# planty1.net
KiCad netlist of a schematic drawn in EAGLE
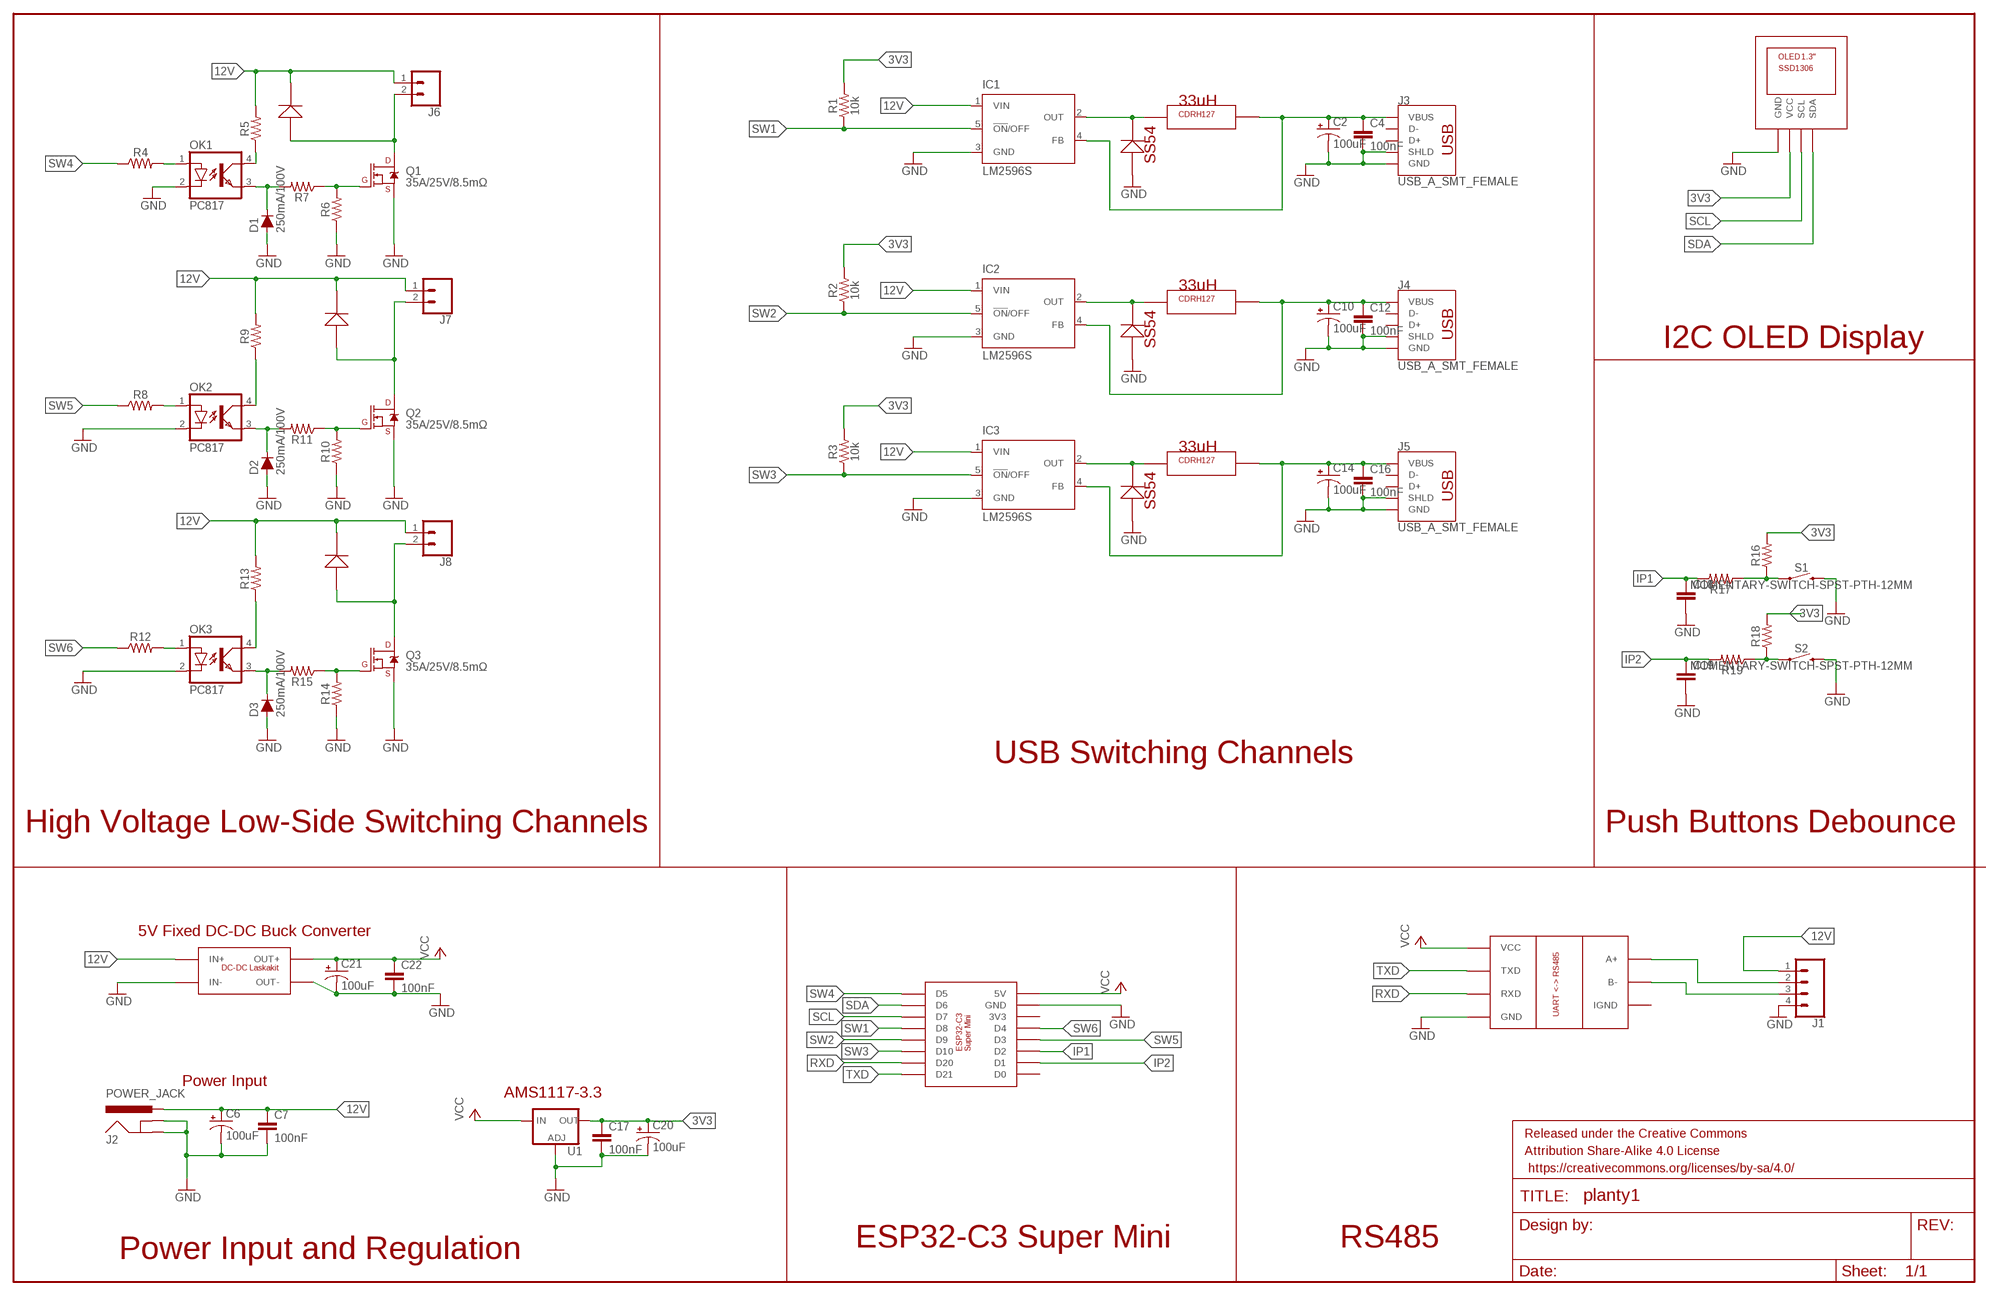
[diagram p0: schematic, sheet 1]

(export (version "E")
  (design (tool "Eeschema 10.0.6"))
  (components
    (comp (ref "C2")
      (value "100uF")
      (footprint "eagle-import:CPOL-RADIAL-2.5MM-6.5MM")
      (libsource (lib "eagle-import") (part "100UF-POLAR-RADIAL-2.5MM-25V-20%"))
    )
    (comp (ref "C4")
      (value "100nF")
      (footprint "eagle-import:1206")
      (libsource (lib "eagle-import") (part "CAP-1206"))
    )
    (comp (ref "C6")
      (value "100uF")
      (footprint "eagle-import:CPOL-RADIAL-2.5MM-6.5MM")
      (libsource (lib "eagle-import") (part "100UF-POLAR-RADIAL-2.5MM-25V-20%"))
    )
    (comp (ref "C7")
      (value "100nF")
      (footprint "eagle-import:1206")
      (libsource (lib "eagle-import") (part "CAP-1206"))
    )
    (comp (ref "C10")
      (value "100uF")
      (footprint "eagle-import:CPOL-RADIAL-2.5MM-6.5MM")
      (libsource (lib "eagle-import") (part "100UF-POLAR-RADIAL-2.5MM-25V-20%"))
    )
    (comp (ref "C12")
      (value "100nF")
      (footprint "eagle-import:1206")
      (libsource (lib "eagle-import") (part "CAP-1206"))
    )
    (comp (ref "C14")
      (value "100uF")
      (footprint "eagle-import:CPOL-RADIAL-2.5MM-6.5MM")
      (libsource (lib "eagle-import") (part "100UF-POLAR-RADIAL-2.5MM-25V-20%"))
    )
    (comp (ref "C16")
      (value "100nF")
      (footprint "eagle-import:1206")
      (libsource (lib "eagle-import") (part "CAP-1206"))
    )
    (comp (ref "C17")
      (value "100nF")
      (footprint "eagle-import:0603")
      (libsource (lib "eagle-import") (part "CAP-0603"))
    )
    (comp (ref "C18")
      (value "CAP-0603")
      (footprint "eagle-import:0603")
      (libsource (lib "eagle-import") (part "CAP-0603"))
    )
    (comp (ref "C19")
      (value "CAP-0603")
      (footprint "eagle-import:0603")
      (libsource (lib "eagle-import") (part "CAP-0603"))
    )
    (comp (ref "C20")
      (value "100uF")
      (footprint "eagle-import:CPOL-RADIAL-2.5MM-6.5MM")
      (libsource (lib "eagle-import") (part "100UF-POLAR-RADIAL-2.5MM-25V-20%"))
    )
    (comp (ref "C21")
      (value "100uF")
      (footprint "eagle-import:CPOL-RADIAL-2.5MM-6.5MM")
      (libsource (lib "eagle-import") (part "100UF-POLAR-RADIAL-2.5MM-25V-20%"))
    )
    (comp (ref "C22")
      (value "100nF")
      (footprint "eagle-import:1206")
      (libsource (lib "eagle-import") (part "CAP-1206"))
    )
    (comp (ref "D1")
      (value "250mA/100V")
      (footprint "eagle-import:SOD-323")
      (libsource (lib "eagle-import") (part "DIODE-BAS16J"))
    )
    (comp (ref "D2")
      (value "250mA/100V")
      (footprint "eagle-import:SOD-323")
      (libsource (lib "eagle-import") (part "DIODE-BAS16J"))
    )
    (comp (ref "D3")
      (value "250mA/100V")
      (footprint "eagle-import:SOD-323")
      (libsource (lib "eagle-import") (part "DIODE-BAS16J"))
    )
    (comp (ref "FRAME1")
      (value "FRAME-LEDGERNO_FOOTPRINT")
      (footprint "eagle-import:DUMMY")
      (libsource (lib "eagle-import") (part "FRAME-LEDGERNO_FOOTPRINT"))
    )
    (comp (ref "IC1")
      (value "LM2596S")
      (footprint "eagle-import:TO263-5")
      (fields (field (name "MF") "NATIONAL SEMICONDUCTOR") (field (name "MPN") "LM2596S-ADJ/NOPB"))
      (libsource (lib "eagle-import") (part "LM2596S"))
    )
    (comp (ref "IC2")
      (value "LM2596S")
      (footprint "eagle-import:TO263-5")
      (fields (field (name "MF") "NATIONAL SEMICONDUCTOR") (field (name "MPN") "LM2596S-ADJ/NOPB"))
      (libsource (lib "eagle-import") (part "LM2596S"))
    )
    (comp (ref "IC3")
      (value "LM2596S")
      (footprint "eagle-import:TO263-5")
      (fields (field (name "MF") "NATIONAL SEMICONDUCTOR") (field (name "MPN") "LM2596S-ADJ/NOPB"))
      (libsource (lib "eagle-import") (part "LM2596S"))
    )
    (comp (ref "J1")
      (value "CONN_04SCREW_LOCK")
      (footprint "eagle-import:SCREWTERMINAL-3.5MM-4_LOCK")
      (libsource (lib "eagle-import") (part "CONN_04SCREW_LOCK"))
    )
    (comp (ref "J2")
      (value "POWER_JACK")
      (footprint "eagle-import:POWER_JACK_PTH")
      (libsource (lib "eagle-import") (part "POWER_JACK"))
    )
    (comp (ref "J3")
      (value "USB_A_SMT_FEMALE")
      (footprint "eagle-import:USB-A-S-SILK-FEMALE")
      (libsource (lib "eagle-import") (part "USB_A_SMT_FEMALE"))
    )
    (comp (ref "J4")
      (value "USB_A_SMT_FEMALE")
      (footprint "eagle-import:USB-A-S-SILK-FEMALE")
      (libsource (lib "eagle-import") (part "USB_A_SMT_FEMALE"))
    )
    (comp (ref "J5")
      (value "USB_A_SMT_FEMALE")
      (footprint "eagle-import:USB-A-S-SILK-FEMALE")
      (libsource (lib "eagle-import") (part "USB_A_SMT_FEMALE"))
    )
    (comp (ref "J6")
      (value "CONN_025MM")
      (footprint "eagle-import:SCREWTERMINAL-5MM-2")
      (libsource (lib "eagle-import") (part "CONN_025MM"))
    )
    (comp (ref "J7")
      (value "CONN_025MM")
      (footprint "eagle-import:SCREWTERMINAL-5MM-2")
      (libsource (lib "eagle-import") (part "CONN_025MM"))
    )
    (comp (ref "J8")
      (value "CONN_025MM")
      (footprint "eagle-import:SCREWTERMINAL-5MM-2")
      (libsource (lib "eagle-import") (part "CONN_025MM"))
    )
    (comp (ref "OK1")
      (value "PC817")
      (footprint "eagle-import:DIL04")
      (fields (field (name "MPN") "PC817X4J000F"))
      (libsource (lib "eagle-import") (part "PC817"))
    )
    (comp (ref "OK2")
      (value "PC817")
      (footprint "eagle-import:DIL04")
      (fields (field (name "MPN") "PC817X4J000F"))
      (libsource (lib "eagle-import") (part "PC817"))
    )
    (comp (ref "OK3")
      (value "PC817")
      (footprint "eagle-import:DIL04")
      (fields (field (name "MPN") "PC817X4J000F"))
      (libsource (lib "eagle-import") (part "PC817"))
    )
    (comp (ref "Q1")
      (value "35A/25V/8.5mΩ")
      (footprint "eagle-import:TO-252_DPAK")
      (libsource (lib "eagle-import") (part "MOSFET-NCH-FDD8780"))
    )
    (comp (ref "Q2")
      (value "35A/25V/8.5mΩ")
      (footprint "eagle-import:TO-252_DPAK")
      (libsource (lib "eagle-import") (part "MOSFET-NCH-FDD8780"))
    )
    (comp (ref "Q3")
      (value "35A/25V/8.5mΩ")
      (footprint "eagle-import:TO-252_DPAK")
      (libsource (lib "eagle-import") (part "MOSFET-NCH-FDD8780"))
    )
    (comp (ref "R1")
      (value "10k")
      (footprint "eagle-import:0603")
      (libsource (lib "eagle-import") (part "RESISTOR0603"))
    )
    (comp (ref "R2")
      (value "10k")
      (footprint "eagle-import:0603")
      (libsource (lib "eagle-import") (part "RESISTOR0603"))
    )
    (comp (ref "R3")
      (value "10k")
      (footprint "eagle-import:0603")
      (libsource (lib "eagle-import") (part "RESISTOR0603"))
    )
    (comp (ref "R4")
      (value "RESISTOR0603")
      (footprint "eagle-import:0603")
      (libsource (lib "eagle-import") (part "RESISTOR0603"))
    )
    (comp (ref "R5")
      (value "RESISTOR0603")
      (footprint "eagle-import:0603")
      (libsource (lib "eagle-import") (part "RESISTOR0603"))
    )
    (comp (ref "R6")
      (value "RESISTOR0603")
      (footprint "eagle-import:0603")
      (libsource (lib "eagle-import") (part "RESISTOR0603"))
    )
    (comp (ref "R7")
      (value "RESISTOR0603")
      (footprint "eagle-import:0603")
      (libsource (lib "eagle-import") (part "RESISTOR0603"))
    )
    (comp (ref "R8")
      (value "RESISTOR0603")
      (footprint "eagle-import:0603")
      (libsource (lib "eagle-import") (part "RESISTOR0603"))
    )
    (comp (ref "R9")
      (value "RESISTOR0603")
      (footprint "eagle-import:0603")
      (libsource (lib "eagle-import") (part "RESISTOR0603"))
    )
    (comp (ref "R10")
      (value "RESISTOR0603")
      (footprint "eagle-import:0603")
      (libsource (lib "eagle-import") (part "RESISTOR0603"))
    )
    (comp (ref "R11")
      (value "RESISTOR0603")
      (footprint "eagle-import:0603")
      (libsource (lib "eagle-import") (part "RESISTOR0603"))
    )
    (comp (ref "R12")
      (value "RESISTOR0603")
      (footprint "eagle-import:0603")
      (libsource (lib "eagle-import") (part "RESISTOR0603"))
    )
    (comp (ref "R13")
      (value "RESISTOR0603")
      (footprint "eagle-import:0603")
      (libsource (lib "eagle-import") (part "RESISTOR0603"))
    )
    (comp (ref "R14")
      (value "RESISTOR0603")
      (footprint "eagle-import:0603")
      (libsource (lib "eagle-import") (part "RESISTOR0603"))
    )
    (comp (ref "R15")
      (value "RESISTOR0603")
      (footprint "eagle-import:0603")
      (libsource (lib "eagle-import") (part "RESISTOR0603"))
    )
    (comp (ref "R16")
      (value "RESISTOR0603")
      (footprint "eagle-import:0603")
      (libsource (lib "eagle-import") (part "RESISTOR0603"))
    )
    (comp (ref "R17")
      (value "RESISTOR0603")
      (footprint "eagle-import:0603")
      (libsource (lib "eagle-import") (part "RESISTOR0603"))
    )
    (comp (ref "R18")
      (value "RESISTOR0603")
      (footprint "eagle-import:0603")
      (libsource (lib "eagle-import") (part "RESISTOR0603"))
    )
    (comp (ref "R19")
      (value "RESISTOR0603")
      (footprint "eagle-import:0603")
      (libsource (lib "eagle-import") (part "RESISTOR0603"))
    )
    (comp (ref "S1")
      (value "MOMENTARY-SWITCH-SPST-PTH-12MM")
      (footprint "eagle-import:TACTILE_SWITCH_PTH_12MM")
      (libsource (lib "eagle-import") (part "MOMENTARY-SWITCH-SPST-PTH-12MM"))
    )
    (comp (ref "S2")
      (value "MOMENTARY-SWITCH-SPST-PTH-12MM")
      (footprint "eagle-import:TACTILE_SWITCH_PTH_12MM")
      (libsource (lib "eagle-import") (part "MOMENTARY-SWITCH-SPST-PTH-12MM"))
    )
    (comp (ref "U$1")
      (value "ESP32-C3-SUPER-MINI")
      (footprint "eagle-import:ESP32-C3-SUPER-MINI")
      (libsource (lib "eagle-import") (part "ESP32-C3-SUPER-MINI"))
    )
    (comp (ref "U$2")
      (value "RS485-UART-CONVERTER")
      (footprint "eagle-import:RS485_MODULE")
      (libsource (lib "eagle-import") (part "RS485-UART-CONVERTER"))
    )
    (comp (ref "U$3")
      (value "CDRH127")
      (footprint "eagle-import:CDRH127")
      (libsource (lib "eagle-import") (part "CDRH127"))
    )
    (comp (ref "U$4")
      (value "SS54")
      (footprint "eagle-import:SS54")
      (libsource (lib "eagle-import") (part "SS54"))
    )
    (comp (ref "U$5")
      (value "DC-DC-LASKAKIT")
      (footprint "eagle-import:DC-DC-MODULE-LASKAKIT")
      (libsource (lib "eagle-import") (part "DC-DC-LASKAKIT"))
    )
    (comp (ref "U$6")
      (value "CDRH127")
      (footprint "eagle-import:CDRH127")
      (libsource (lib "eagle-import") (part "CDRH127"))
    )
    (comp (ref "U$7")
      (value "SS54")
      (footprint "eagle-import:SS54")
      (libsource (lib "eagle-import") (part "SS54"))
    )
    (comp (ref "U$8")
      (value "CDRH127 - 33uH")
      (footprint "eagle-import:CDRH127")
      (libsource (lib "eagle-import") (part "CDRH127"))
    )
    (comp (ref "U$9")
      (value "SS54")
      (footprint "eagle-import:SS54")
      (libsource (lib "eagle-import") (part "SS54"))
    )
    (comp (ref "U$10")
      (value "SS54")
      (footprint "eagle-import:SS54")
      (libsource (lib "eagle-import") (part "SS54"))
    )
    (comp (ref "U$11")
      (value "SS54")
      (footprint "eagle-import:SS54")
      (libsource (lib "eagle-import") (part "SS54"))
    )
    (comp (ref "U$12")
      (value "SS54")
      (footprint "eagle-import:SS54")
      (libsource (lib "eagle-import") (part "SS54"))
    )
    (comp (ref "U$13")
      (value "OLED_0.96_I2C")
      (footprint "eagle-import:OLED_0.96")
      (libsource (lib "eagle-import") (part "OLED_0.96_I2C"))
    )
    (comp (ref "U1")
      (value "V_REG_LM1117SOT223")
      (footprint "eagle-import:SOT223")
      (libsource (lib "eagle-import") (part "V_REG_LM1117SOT223"))
    )
  )
  (nets
    (net (code "1") (name "3V3") (class "Default")
      (node (ref "C17") (pin "1") (pinfunction "1_1") (pintype "passive"))
      (node (ref "C20") (pin "1") (pinfunction "+_1") (pintype "passive"))
      (node (ref "R1") (pin "2") (pinfunction "2_2") (pintype "passive"))
      (node (ref "R16") (pin "2") (pinfunction "2_2") (pintype "passive"))
      (node (ref "R18") (pin "2") (pinfunction "2_2") (pintype "passive"))
      (node (ref "R2") (pin "2") (pinfunction "2_2") (pintype "passive"))
      (node (ref "R3") (pin "2") (pinfunction "2_2") (pintype "passive"))
      (node (ref "U$13") (pin "P$2") (pinfunction "VCC_P$2") (pintype "bidirectional"))
      (node (ref "U1") (pin "2") (pinfunction "OUT_2") (pintype "output"))
      (node (ref "U1") (pin "4") (pinfunction "OUT_4") (pintype "output"))
    )
    (net (code "2") (name "12V") (class "Default")
      (node (ref "C6") (pin "1") (pinfunction "+_1") (pintype "passive"))
      (node (ref "C7") (pin "1") (pinfunction "1_1") (pintype "passive"))
      (node (ref "IC1") (pin "1") (pinfunction "VIN_1") (pintype "input"))
      (node (ref "IC2") (pin "1") (pinfunction "VIN_1") (pintype "input"))
      (node (ref "IC3") (pin "1") (pinfunction "VIN_1") (pintype "input"))
      (node (ref "J1") (pin "1") (pinfunction "1_1") (pintype "passive"))
      (node (ref "J2") (pin "PWR") (pinfunction "PWR_PWR") (pintype "bidirectional"))
      (node (ref "J6") (pin "1") (pinfunction "1_1") (pintype "passive"))
      (node (ref "J7") (pin "1") (pinfunction "1_1") (pintype "passive"))
      (node (ref "J8") (pin "1") (pinfunction "1_1") (pintype "passive"))
      (node (ref "R13") (pin "2") (pinfunction "2_2") (pintype "passive"))
      (node (ref "R5") (pin "2") (pinfunction "2_2") (pintype "passive"))
      (node (ref "R9") (pin "2") (pinfunction "2_2") (pintype "passive"))
      (node (ref "U$10") (pin "N") (pinfunction "N_N") (pintype "bidirectional"))
      (node (ref "U$11") (pin "N") (pinfunction "N_N") (pintype "bidirectional"))
      (node (ref "U$12") (pin "N") (pinfunction "N_N") (pintype "bidirectional"))
      (node (ref "U$5") (pin "IN+") (pinfunction "IN+_IN+") (pintype "bidirectional"))
    )
    (net (code "3") (name "GND") (class "Default")
      (node (ref "C10") (pin "2") (pinfunction "-_2") (pintype "passive"))
      (node (ref "C12") (pin "2") (pinfunction "2_2") (pintype "passive"))
      (node (ref "C14") (pin "2") (pinfunction "-_2") (pintype "passive"))
      (node (ref "C16") (pin "2") (pinfunction "2_2") (pintype "passive"))
      (node (ref "C17") (pin "2") (pinfunction "2_2") (pintype "passive"))
      (node (ref "C18") (pin "2") (pinfunction "2_2") (pintype "passive"))
      (node (ref "C19") (pin "2") (pinfunction "2_2") (pintype "passive"))
      (node (ref "C2") (pin "2") (pinfunction "-_2") (pintype "passive"))
      (node (ref "C20") (pin "2") (pinfunction "-_2") (pintype "passive"))
      (node (ref "C21") (pin "2") (pinfunction "-_2") (pintype "passive"))
      (node (ref "C22") (pin "2") (pinfunction "2_2") (pintype "passive"))
      (node (ref "C4") (pin "2") (pinfunction "2_2") (pintype "passive"))
      (node (ref "C6") (pin "2") (pinfunction "-_2") (pintype "passive"))
      (node (ref "C7") (pin "2") (pinfunction "2_2") (pintype "passive"))
      (node (ref "D1") (pin "A") (pinfunction "A_A") (pintype "passive"))
      (node (ref "D2") (pin "A") (pinfunction "A_A") (pintype "passive"))
      (node (ref "D3") (pin "A") (pinfunction "A_A") (pintype "passive"))
      (node (ref "IC1") (pin "3") (pinfunction "GND_3") (pintype "power_in"))
      (node (ref "IC2") (pin "3") (pinfunction "GND_3") (pintype "power_in"))
      (node (ref "IC3") (pin "3") (pinfunction "GND_3") (pintype "power_in"))
      (node (ref "J1") (pin "4") (pinfunction "4_4") (pintype "passive"))
      (node (ref "J2") (pin "GND") (pinfunction "GND_GND") (pintype "bidirectional"))
      (node (ref "J2") (pin "GNDBREAK") (pinfunction "GNDBREAK_GNDBREAK") (pintype "bidirectional"))
      (node (ref "J3") (pin "GND") (pinfunction "GND_GND") (pintype "power_in"))
      (node (ref "J3") (pin "SHLD1") (pinfunction "SHLD_SHLD1") (pintype "bidirectional"))
      (node (ref "J3") (pin "SHLD2") (pinfunction "SHLD_SHLD2") (pintype "bidirectional"))
      (node (ref "J4") (pin "GND") (pinfunction "GND_GND") (pintype "power_in"))
      (node (ref "J4") (pin "SHLD1") (pinfunction "SHLD_SHLD1") (pintype "bidirectional"))
      (node (ref "J4") (pin "SHLD2") (pinfunction "SHLD_SHLD2") (pintype "bidirectional"))
      (node (ref "J5") (pin "GND") (pinfunction "GND_GND") (pintype "power_in"))
      (node (ref "J5") (pin "SHLD1") (pinfunction "SHLD_SHLD1") (pintype "bidirectional"))
      (node (ref "J5") (pin "SHLD2") (pinfunction "SHLD_SHLD2") (pintype "bidirectional"))
      (node (ref "OK1") (pin "2") (pinfunction "C_2") (pintype "passive"))
      (node (ref "OK2") (pin "2") (pinfunction "C_2") (pintype "passive"))
      (node (ref "OK3") (pin "2") (pinfunction "C_2") (pintype "passive"))
      (node (ref "Q1") (pin "3") (pinfunction "S_3") (pintype "bidirectional"))
      (node (ref "Q2") (pin "3") (pinfunction "S_3") (pintype "bidirectional"))
      (node (ref "Q3") (pin "3") (pinfunction "S_3") (pintype "bidirectional"))
      (node (ref "R10") (pin "1") (pinfunction "1_1") (pintype "passive"))
      (node (ref "R14") (pin "1") (pinfunction "1_1") (pintype "passive"))
      (node (ref "R6") (pin "1") (pinfunction "1_1") (pintype "passive"))
      (node (ref "S1") (pin "3") (pinfunction "2_3") (pintype "passive"))
      (node (ref "S2") (pin "3") (pinfunction "2_3") (pintype "passive"))
      (node (ref "U$1") (pin "P$15") (pinfunction "GND_P$15") (pintype "bidirectional"))
      (node (ref "U$13") (pin "P$1") (pinfunction "GND_P$1") (pintype "bidirectional"))
      (node (ref "U$2") (pin "GND") (pinfunction "GND_GND") (pintype "bidirectional"))
      (node (ref "U$4") (pin "P") (pinfunction "P_P") (pintype "bidirectional"))
      (node (ref "U$5") (pin "IN-") (pinfunction "IN-_IN-") (pintype "bidirectional"))
      (node (ref "U$5") (pin "OUT-") (pinfunction "OUT-_OUT-") (pintype "bidirectional"))
      (node (ref "U$7") (pin "P") (pinfunction "P_P") (pintype "bidirectional"))
      (node (ref "U$9") (pin "P") (pinfunction "P_P") (pintype "bidirectional"))
      (node (ref "U1") (pin "1") (pinfunction "ADJ_1") (pintype "input"))
    )
    (net (code "4") (name "IP1") (class "Default")
      (node (ref "C18") (pin "1") (pinfunction "1_1") (pintype "passive"))
      (node (ref "R17") (pin "2") (pinfunction "2_2") (pintype "passive"))
      (node (ref "U$1") (pin "P$11") (pinfunction "D2_P$11") (pintype "bidirectional"))
    )
    (net (code "5") (name "IP2") (class "Default")
      (node (ref "C19") (pin "1") (pinfunction "1_1") (pintype "passive"))
      (node (ref "R19") (pin "2") (pinfunction "2_2") (pintype "passive"))
      (node (ref "U$1") (pin "P$10") (pinfunction "D1_P$10") (pintype "bidirectional"))
    )
    (net (code "6") (name "Net-(C2-+)") (class "Default")
      (node (ref "C2") (pin "1") (pinfunction "+_1") (pintype "passive"))
      (node (ref "C4") (pin "1") (pinfunction "1_1") (pintype "passive"))
      (node (ref "IC1") (pin "4") (pinfunction "FB_4") (pintype "input"))
      (node (ref "J3") (pin "VBUS") (pinfunction "VBUS_VBUS") (pintype "power_in"))
      (node (ref "U$3") (pin "P$2") (pinfunction "P$2_P$2") (pintype "bidirectional"))
    )
    (net (code "7") (name "Net-(C10-+)") (class "Default")
      (node (ref "C10") (pin "1") (pinfunction "+_1") (pintype "passive"))
      (node (ref "C12") (pin "1") (pinfunction "1_1") (pintype "passive"))
      (node (ref "IC2") (pin "4") (pinfunction "FB_4") (pintype "input"))
      (node (ref "J4") (pin "VBUS") (pinfunction "VBUS_VBUS") (pintype "power_in"))
      (node (ref "U$6") (pin "P$2") (pinfunction "P$2_P$2") (pintype "bidirectional"))
    )
    (net (code "8") (name "Net-(C14-+)") (class "Default")
      (node (ref "C14") (pin "1") (pinfunction "+_1") (pintype "passive"))
      (node (ref "C16") (pin "1") (pinfunction "1_1") (pintype "passive"))
      (node (ref "IC3") (pin "4") (pinfunction "FB_4") (pintype "input"))
      (node (ref "J5") (pin "VBUS") (pinfunction "VBUS_VBUS") (pintype "power_in"))
      (node (ref "U$8") (pin "P$2") (pinfunction "P$2_P$2") (pintype "bidirectional"))
    )
    (net (code "9") (name "Net-(IC1-OUT)") (class "Default")
      (node (ref "IC1") (pin "2") (pinfunction "OUT_2") (pintype "output"))
      (node (ref "U$3") (pin "P$1") (pinfunction "P$1_P$1") (pintype "bidirectional"))
      (node (ref "U$4") (pin "N") (pinfunction "N_N") (pintype "bidirectional"))
    )
    (net (code "10") (name "Net-(IC2-OUT)") (class "Default")
      (node (ref "IC2") (pin "2") (pinfunction "OUT_2") (pintype "output"))
      (node (ref "U$6") (pin "P$1") (pinfunction "P$1_P$1") (pintype "bidirectional"))
      (node (ref "U$7") (pin "N") (pinfunction "N_N") (pintype "bidirectional"))
    )
    (net (code "11") (name "Net-(IC3-OUT)") (class "Default")
      (node (ref "IC3") (pin "2") (pinfunction "OUT_2") (pintype "output"))
      (node (ref "U$8") (pin "P$1") (pinfunction "P$1_P$1") (pintype "bidirectional"))
      (node (ref "U$9") (pin "N") (pinfunction "N_N") (pintype "bidirectional"))
    )
    (net (code "12") (name "Net-(J1-Pad2)") (class "Default")
      (node (ref "J1") (pin "2") (pinfunction "2_2") (pintype "passive"))
      (node (ref "U$2") (pin "A+") (pinfunction "A+_A+") (pintype "bidirectional"))
    )
    (net (code "13") (name "Net-(J1-Pad3)") (class "Default")
      (node (ref "J1") (pin "3") (pinfunction "3_3") (pintype "passive"))
      (node (ref "U$2") (pin "B-") (pinfunction "B-_B-") (pintype "bidirectional"))
    )
    (net (code "14") (name "Net-(OK1-A)") (class "Default")
      (node (ref "OK1") (pin "1") (pinfunction "A_1") (pintype "passive"))
      (node (ref "R4") (pin "2") (pinfunction "2_2") (pintype "passive"))
    )
    (net (code "15") (name "Net-(OK1-COL)") (class "Default")
      (node (ref "OK1") (pin "4") (pinfunction "COL_4") (pintype "passive"))
      (node (ref "R5") (pin "1") (pinfunction "1_1") (pintype "passive"))
    )
    (net (code "16") (name "Net-(OK1-EMIT)") (class "Default")
      (node (ref "D1") (pin "C") (pinfunction "C_C") (pintype "passive"))
      (node (ref "OK1") (pin "3") (pinfunction "EMIT_3") (pintype "passive"))
      (node (ref "R7") (pin "2") (pinfunction "2_2") (pintype "passive"))
    )
    (net (code "17") (name "Net-(OK2-A)") (class "Default")
      (node (ref "OK2") (pin "1") (pinfunction "A_1") (pintype "passive"))
      (node (ref "R8") (pin "2") (pinfunction "2_2") (pintype "passive"))
    )
    (net (code "18") (name "Net-(OK2-COL)") (class "Default")
      (node (ref "OK2") (pin "4") (pinfunction "COL_4") (pintype "passive"))
      (node (ref "R9") (pin "1") (pinfunction "1_1") (pintype "passive"))
    )
    (net (code "19") (name "Net-(OK2-EMIT)") (class "Default")
      (node (ref "D2") (pin "C") (pinfunction "C_C") (pintype "passive"))
      (node (ref "OK2") (pin "3") (pinfunction "EMIT_3") (pintype "passive"))
      (node (ref "R11") (pin "2") (pinfunction "2_2") (pintype "passive"))
    )
    (net (code "20") (name "Net-(OK3-A)") (class "Default")
      (node (ref "OK3") (pin "1") (pinfunction "A_1") (pintype "passive"))
      (node (ref "R12") (pin "2") (pinfunction "2_2") (pintype "passive"))
    )
    (net (code "21") (name "Net-(OK3-COL)") (class "Default")
      (node (ref "OK3") (pin "4") (pinfunction "COL_4") (pintype "passive"))
      (node (ref "R13") (pin "1") (pinfunction "1_1") (pintype "passive"))
    )
    (net (code "22") (name "Net-(OK3-EMIT)") (class "Default")
      (node (ref "D3") (pin "C") (pinfunction "C_C") (pintype "passive"))
      (node (ref "OK3") (pin "3") (pinfunction "EMIT_3") (pintype "passive"))
      (node (ref "R15") (pin "2") (pinfunction "2_2") (pintype "passive"))
    )
    (net (code "23") (name "Net-(Q1-D)") (class "Default")
      (node (ref "J6") (pin "2") (pinfunction "2_2") (pintype "passive"))
      (node (ref "Q1") (pin "2") (pinfunction "D_2") (pintype "bidirectional"))
      (node (ref "U$10") (pin "P") (pinfunction "P_P") (pintype "bidirectional"))
    )
    (net (code "24") (name "Net-(Q1-G)") (class "Default")
      (node (ref "Q1") (pin "1") (pinfunction "G_1") (pintype "bidirectional"))
      (node (ref "R6") (pin "2") (pinfunction "2_2") (pintype "passive"))
      (node (ref "R7") (pin "1") (pinfunction "1_1") (pintype "passive"))
    )
    (net (code "25") (name "Net-(Q2-D)") (class "Default")
      (node (ref "J7") (pin "2") (pinfunction "2_2") (pintype "passive"))
      (node (ref "Q2") (pin "2") (pinfunction "D_2") (pintype "bidirectional"))
      (node (ref "U$11") (pin "P") (pinfunction "P_P") (pintype "bidirectional"))
    )
    (net (code "26") (name "Net-(Q2-G)") (class "Default")
      (node (ref "Q2") (pin "1") (pinfunction "G_1") (pintype "bidirectional"))
      (node (ref "R10") (pin "2") (pinfunction "2_2") (pintype "passive"))
      (node (ref "R11") (pin "1") (pinfunction "1_1") (pintype "passive"))
    )
    (net (code "27") (name "Net-(Q3-D)") (class "Default")
      (node (ref "J8") (pin "2") (pinfunction "2_2") (pintype "passive"))
      (node (ref "Q3") (pin "2") (pinfunction "D_2") (pintype "bidirectional"))
      (node (ref "U$12") (pin "P") (pinfunction "P_P") (pintype "bidirectional"))
    )
    (net (code "28") (name "Net-(Q3-G)") (class "Default")
      (node (ref "Q3") (pin "1") (pinfunction "G_1") (pintype "bidirectional"))
      (node (ref "R14") (pin "2") (pinfunction "2_2") (pintype "passive"))
      (node (ref "R15") (pin "1") (pinfunction "1_1") (pintype "passive"))
    )
    (net (code "29") (name "Net-(R16-Pad1)") (class "Default")
      (node (ref "R16") (pin "1") (pinfunction "1_1") (pintype "passive"))
      (node (ref "R17") (pin "1") (pinfunction "1_1") (pintype "passive"))
      (node (ref "S1") (pin "1") (pinfunction "1_1") (pintype "passive"))
    )
    (net (code "30") (name "Net-(R18-Pad1)") (class "Default")
      (node (ref "R18") (pin "1") (pinfunction "1_1") (pintype "passive"))
      (node (ref "R19") (pin "1") (pinfunction "1_1") (pintype "passive"))
      (node (ref "S2") (pin "1") (pinfunction "1_1") (pintype "passive"))
    )
    (net (code "31") (name "RXD") (class "Default")
      (node (ref "U$1") (pin "P$7") (pinfunction "D20_P$7") (pintype "bidirectional"))
      (node (ref "U$2") (pin "RXD") (pinfunction "RXD_RXD") (pintype "bidirectional"))
    )
    (net (code "32") (name "SCL") (class "Default")
      (node (ref "U$1") (pin "P$3") (pinfunction "D7_P$3") (pintype "bidirectional"))
      (node (ref "U$13") (pin "P$3") (pinfunction "SCL_P$3") (pintype "bidirectional"))
    )
    (net (code "33") (name "SDA") (class "Default")
      (node (ref "U$1") (pin "P$2") (pinfunction "D6_P$2") (pintype "bidirectional"))
      (node (ref "U$13") (pin "P$4") (pinfunction "SDA_P$4") (pintype "bidirectional"))
    )
    (net (code "34") (name "SW1") (class "Default")
      (node (ref "IC1") (pin "5") (pinfunction "~{ON}/OFF_5") (pintype "input"))
      (node (ref "R1") (pin "1") (pinfunction "1_1") (pintype "passive"))
      (node (ref "U$1") (pin "P$4") (pinfunction "D8_P$4") (pintype "bidirectional"))
    )
    (net (code "35") (name "SW2") (class "Default")
      (node (ref "IC2") (pin "5") (pinfunction "~{ON}/OFF_5") (pintype "input"))
      (node (ref "R2") (pin "1") (pinfunction "1_1") (pintype "passive"))
      (node (ref "U$1") (pin "P$5") (pinfunction "D9_P$5") (pintype "bidirectional"))
    )
    (net (code "36") (name "SW3") (class "Default")
      (node (ref "IC3") (pin "5") (pinfunction "~{ON}/OFF_5") (pintype "input"))
      (node (ref "R3") (pin "1") (pinfunction "1_1") (pintype "passive"))
      (node (ref "U$1") (pin "P$6") (pinfunction "D10_P$6") (pintype "bidirectional"))
    )
    (net (code "37") (name "SW4") (class "Default")
      (node (ref "R4") (pin "1") (pinfunction "1_1") (pintype "passive"))
      (node (ref "U$1") (pin "P$1") (pinfunction "D5_P$1") (pintype "bidirectional"))
    )
    (net (code "38") (name "SW5") (class "Default")
      (node (ref "R8") (pin "1") (pinfunction "1_1") (pintype "passive"))
      (node (ref "U$1") (pin "P$12") (pinfunction "D3_P$12") (pintype "bidirectional"))
    )
    (net (code "39") (name "SW6") (class "Default")
      (node (ref "R12") (pin "1") (pinfunction "1_1") (pintype "passive"))
      (node (ref "U$1") (pin "P$13") (pinfunction "D4_P$13") (pintype "bidirectional"))
    )
    (net (code "40") (name "TXD") (class "Default")
      (node (ref "U$1") (pin "P$8") (pinfunction "D21_P$8") (pintype "bidirectional"))
      (node (ref "U$2") (pin "TXD") (pinfunction "TXD_TXD") (pintype "bidirectional"))
    )
    (net (code "41") (name "VCC") (class "Default")
      (node (ref "C21") (pin "1") (pinfunction "+_1") (pintype "passive"))
      (node (ref "C22") (pin "1") (pinfunction "1_1") (pintype "passive"))
      (node (ref "U$1") (pin "P$16") (pinfunction "5V_P$16") (pintype "bidirectional"))
      (node (ref "U$2") (pin "VCC") (pinfunction "VCC_VCC") (pintype "bidirectional"))
      (node (ref "U$5") (pin "OUT+") (pinfunction "OUT+_OUT+") (pintype "bidirectional"))
      (node (ref "U1") (pin "3") (pinfunction "IN_3") (pintype "input"))
    )
    (net (code "42") (name "unconnected-(J3-PadD+)") (class "Default")
      (node (ref "J3") (pin "D+") (pinfunction "D+_D+") (pintype "bidirectional"))
    )
    (net (code "43") (name "unconnected-(J3-PadD-)") (class "Default")
      (node (ref "J3") (pin "D-") (pinfunction "D-_D-") (pintype "bidirectional"))
    )
    (net (code "44") (name "unconnected-(J4-PadD+)") (class "Default")
      (node (ref "J4") (pin "D+") (pinfunction "D+_D+") (pintype "bidirectional"))
    )
    (net (code "45") (name "unconnected-(J4-PadD-)") (class "Default")
      (node (ref "J4") (pin "D-") (pinfunction "D-_D-") (pintype "bidirectional"))
    )
    (net (code "46") (name "unconnected-(J5-PadD+)") (class "Default")
      (node (ref "J5") (pin "D+") (pinfunction "D+_D+") (pintype "bidirectional"))
    )
    (net (code "47") (name "unconnected-(J5-PadD-)") (class "Default")
      (node (ref "J5") (pin "D-") (pinfunction "D-_D-") (pintype "bidirectional"))
    )
    (net (code "48") (name "unconnected-(U$1-3V3-PadP$14)") (class "Default")
      (node (ref "U$1") (pin "P$14") (pinfunction "3V3_P$14") (pintype "bidirectional"))
    )
    (net (code "49") (name "unconnected-(U$1-D0-PadP$9)") (class "Default")
      (node (ref "U$1") (pin "P$9") (pinfunction "D0_P$9") (pintype "bidirectional"))
    )
    (net (code "50") (name "unconnected-(U$2-IGND-PadISOGND)") (class "Default")
      (node (ref "U$2") (pin "ISOGND") (pinfunction "IGND_ISOGND") (pintype "bidirectional"))
    )
  )
)
